# Mainboard_MCU_Func.net
KiCad netlist of a schematic drawn in Altium Designer
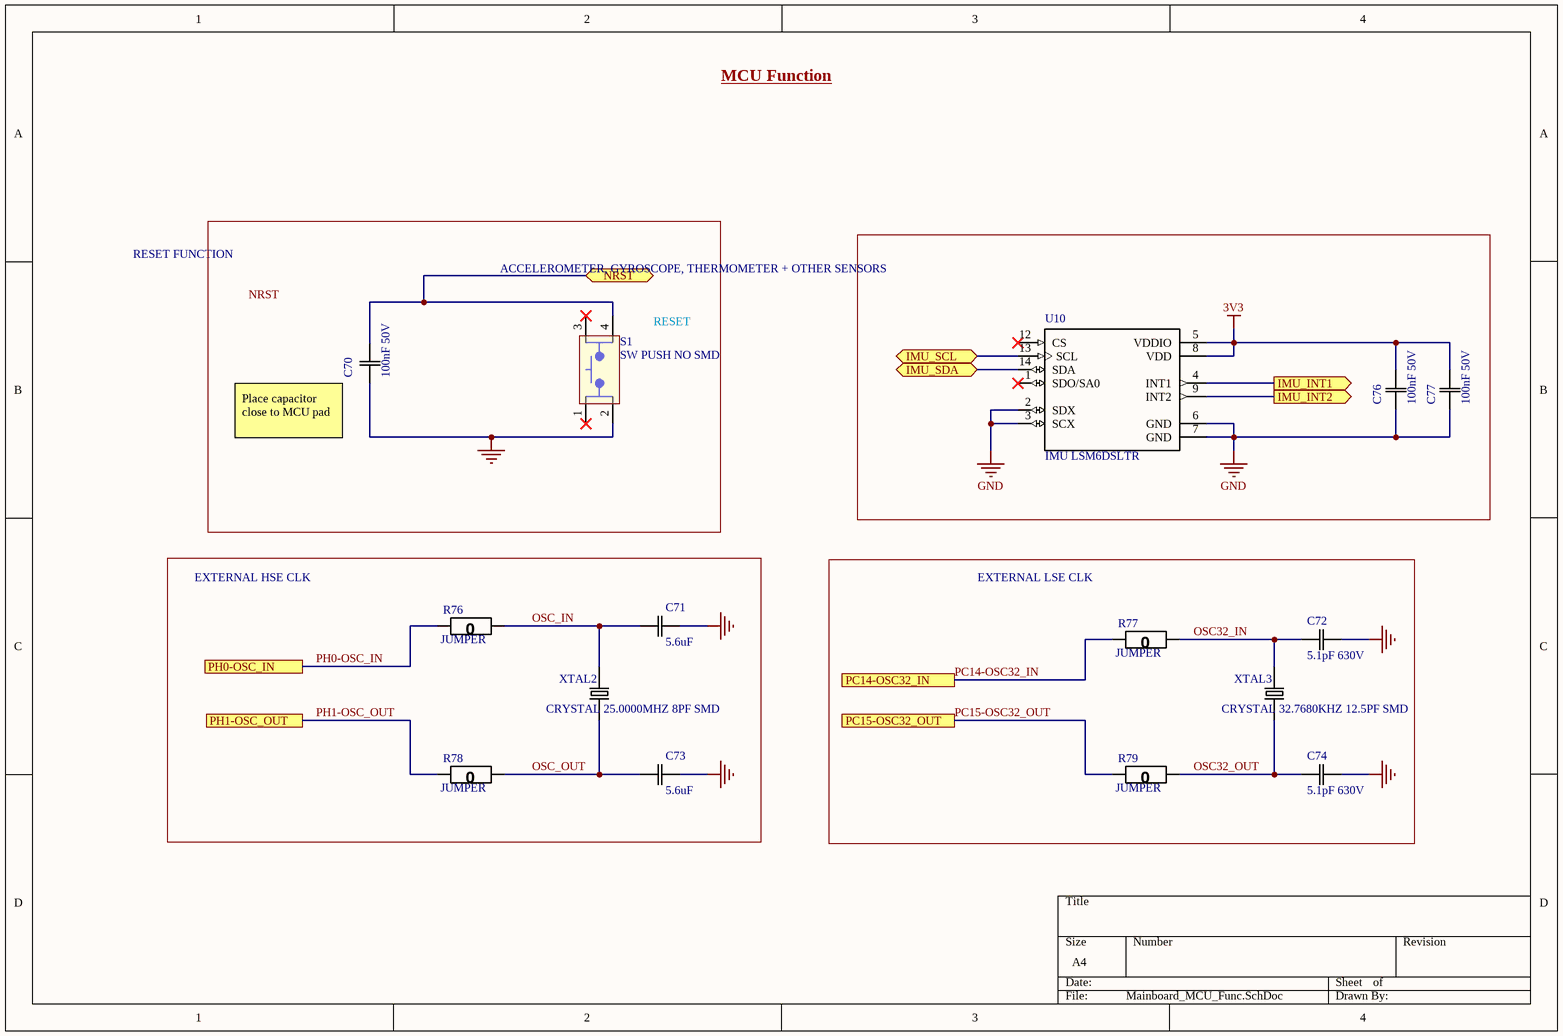
[diagram p0: Mainboard_MCU_Func.SchDoc]

(export (version "E")
  (design (tool "Eeschema 10.0.6"))
  (components
    (comp (ref "C70")
      (value "100nF 50V")
      (footprint "0805")
      (description "CAP CER 0.1UF 50V X7R 0805")
      (fields (field (name "TOLERANCE") "10%"))
      (libsource (lib "AltiumLibraries") (part "CAP 100nF 50V"))
    )
    (comp (ref "C71")
      (value "5.6uF")
      (footprint "0805")
      (description "CAP CER 5.6UF 6.3V X5R 0805")
      (fields (field (name "TOLERANCE") "10%"))
      (libsource (lib "AltiumLibraries") (part "CAP 5.6uF 6.3V"))
    )
    (comp (ref "C72")
      (value "5.1pF 630V")
      (footprint "0805")
      (description "CAP CER 5.1PF 630V C0G/NP0 0805")
      (fields (field (name "TOLERANCE") "10%"))
      (libsource (lib "AltiumLibraries") (part "CAP 5.1pF 630V"))
    )
    (comp (ref "C73")
      (value "5.6uF")
      (footprint "0805")
      (description "CAP CER 5.6UF 6.3V X5R 0805")
      (fields (field (name "TOLERANCE") "10%"))
      (libsource (lib "AltiumLibraries") (part "CAP 5.6uF 6.3V"))
    )
    (comp (ref "C74")
      (value "5.1pF 630V")
      (footprint "0805")
      (description "CAP CER 5.1PF 630V C0G/NP0 0805")
      (fields (field (name "TOLERANCE") "10%"))
      (libsource (lib "AltiumLibraries") (part "CAP 5.1pF 630V"))
    )
    (comp (ref "C76")
      (value "100nF 50V")
      (footprint "0805")
      (description "CAP CER 0.1UF 50V X7R 0805")
      (fields (field (name "TOLERANCE") "10%"))
      (libsource (lib "AltiumLibraries") (part "CAP 100nF 50V"))
    )
    (comp (ref "C77")
      (value "100nF 50V")
      (footprint "0805")
      (description "CAP CER 0.1UF 50V X7R 0805")
      (fields (field (name "TOLERANCE") "10%"))
      (libsource (lib "AltiumLibraries") (part "CAP 100nF 50V"))
    )
    (comp (ref "R76")
      (value "JUMPER")
      (footprint "0805")
      (description "RES SMD 0 OHM JUMPER GENERIC 0805")
      (libsource (lib "AltiumLibraries") (part "RES 0 JUMPER"))
    )
    (comp (ref "R77")
      (value "JUMPER")
      (footprint "0805")
      (description "RES SMD 0 OHM JUMPER GENERIC 0805")
      (libsource (lib "AltiumLibraries") (part "RES 0 JUMPER"))
    )
    (comp (ref "R78")
      (value "JUMPER")
      (footprint "0805")
      (description "RES SMD 0 OHM JUMPER GENERIC 0805")
      (libsource (lib "AltiumLibraries") (part "RES 0 JUMPER"))
    )
    (comp (ref "R79")
      (value "JUMPER")
      (footprint "0805")
      (description "RES SMD 0 OHM JUMPER GENERIC 0805")
      (libsource (lib "AltiumLibraries") (part "RES 0 JUMPER"))
    )
    (comp (ref "S1")
      (value "SW PUSH NO SMD")
      (footprint "TL3305")
      (description "Tactile Switch SPST-NO Top Actuated Surface Mount 12V 50mA")
      (fields (field (name "MF") "E-Switch") (field (name "MP") "TL3305BF260QG"))
      (libsource (lib "AltiumLibraries") (part "SW PUSH NO SMD"))
    )
    (comp (ref "U10")
      (value "IMU LSM6DSLTR")
      (footprint "LGA-14")
      (description "IMU ACCEL/GYRO I2C/SPI 14LGA")
      (fields (field (name "MP") "LSM6DSLTR") (field (name "MF") "STMicroelectronics"))
      (libsource (lib "AltiumLibraries") (part "IMU LSM6DSLTR"))
    )
    (comp (ref "XTAL2")
      (value "CRYSTAL 25.0000MHZ 8PF SMD")
      (footprint "SMD-2")
      (description "25MHz ±50ppm Crystal 8pF 70 Ohms 2-SMD, No Lead")
      (fields (field (name "MP") "NX5032GA-25.000000MHZ-LN-CD-1") (field (name "MF") "NDK America, Inc."))
      (libsource (lib "AltiumLibraries") (part "XTAL 25MHZ 8PF SMD"))
    )
    (comp (ref "XTAL3")
      (value "CRYSTAL 32.7680KHZ 12.5PF SMD")
      (footprint "SMD-2")
      (description "32.768kHz ±20ppm Crystal 12.5pF 70 kOhms 2-SMD, No Lead")
      (fields (field (name "MP") "NX3215SA-32.768K-STD-MUA-8") (field (name "MF") "NDK America, Inc."))
      (libsource (lib "AltiumLibraries") (part "XTAL 32.7680KHZ 12.5PF SMD"))
    )
  )
  (nets
    (net (code "1") (name "/IMU_INT1") (class "Default")
      (node (ref "U10") (pin "4") (pinfunction "INT1_4") (pintype "output"))
    )
    (net (code "2") (name "/IMU_INT2") (class "Default")
      (node (ref "U10") (pin "9") (pinfunction "INT2_9") (pintype "output"))
    )
    (net (code "3") (name "/IMU_SCL") (class "Default")
      (node (ref "U10") (pin "13") (pinfunction "SCL_13") (pintype "input"))
    )
    (net (code "4") (name "/IMU_SDA") (class "Default")
      (node (ref "U10") (pin "14") (pinfunction "SDA_14") (pintype "bidirectional"))
    )
    (net (code "5") (name "/NRST") (class "Default")
      (node (ref "C70") (pin "2") (pinfunction "C2_2") (pintype "passive"))
      (node (ref "S1") (pin "4") (pinfunction "4_4") (pintype "passive"))
    )
    (net (code "6") (name "/OSC32_IN") (class "Default")
      (node (ref "C72") (pin "1") (pinfunction "C1_1") (pintype "passive"))
      (node (ref "R77") (pin "1") (pinfunction "R1_1") (pintype "passive"))
      (node (ref "XTAL3") (pin "2") (pinfunction "2_2") (pintype "passive"))
    )
    (net (code "7") (name "/OSC32_OUT") (class "Default")
      (node (ref "C74") (pin "1") (pinfunction "C1_1") (pintype "passive"))
      (node (ref "R79") (pin "1") (pinfunction "R1_1") (pintype "passive"))
      (node (ref "XTAL3") (pin "1") (pinfunction "1_1") (pintype "passive"))
    )
    (net (code "8") (name "/OSC_IN") (class "Default")
      (node (ref "C71") (pin "1") (pinfunction "C1_1") (pintype "passive"))
      (node (ref "R76") (pin "1") (pinfunction "R1_1") (pintype "passive"))
      (node (ref "XTAL2") (pin "2") (pinfunction "2_2") (pintype "passive"))
    )
    (net (code "9") (name "/OSC_OUT") (class "Default")
      (node (ref "C73") (pin "1") (pinfunction "C1_1") (pintype "passive"))
      (node (ref "R78") (pin "1") (pinfunction "R1_1") (pintype "passive"))
      (node (ref "XTAL2") (pin "1") (pinfunction "1_1") (pintype "passive"))
    )
    (net (code "10") (name "/PC14-OSC32_IN") (class "Default")
      (node (ref "R77") (pin "2") (pinfunction "R2_2") (pintype "passive"))
    )
    (net (code "11") (name "/PC15-OSC32_OUT") (class "Default")
      (node (ref "R79") (pin "2") (pinfunction "R2_2") (pintype "passive"))
    )
    (net (code "12") (name "/PH0-OSC_IN") (class "Default")
      (node (ref "R76") (pin "2") (pinfunction "R2_2") (pintype "passive"))
    )
    (net (code "13") (name "/PH1-OSC_OUT") (class "Default")
      (node (ref "R78") (pin "2") (pinfunction "R2_2") (pintype "passive"))
    )
    (net (code "14") (name "3V3") (class "Default")
      (node (ref "C76") (pin "2") (pinfunction "C2_2") (pintype "passive"))
      (node (ref "C77") (pin "2") (pinfunction "C2_2") (pintype "passive"))
      (node (ref "U10") (pin "5") (pinfunction "VDDIO_5") (pintype "power_in"))
      (node (ref "U10") (pin "8") (pinfunction "VDD_8") (pintype "power_in"))
    )
    (net (code "15") (name "GND") (class "Default")
      (node (ref "C70") (pin "1") (pinfunction "C1_1") (pintype "passive"))
      (node (ref "C71") (pin "2") (pinfunction "C2_2") (pintype "passive"))
      (node (ref "C72") (pin "2") (pinfunction "C2_2") (pintype "passive"))
      (node (ref "C73") (pin "2") (pinfunction "C2_2") (pintype "passive"))
      (node (ref "C74") (pin "2") (pinfunction "C2_2") (pintype "passive"))
      (node (ref "C76") (pin "1") (pinfunction "C1_1") (pintype "passive"))
      (node (ref "C77") (pin "1") (pinfunction "C1_1") (pintype "passive"))
      (node (ref "S1") (pin "2") (pinfunction "2_2") (pintype "passive"))
      (node (ref "U10") (pin "2") (pinfunction "SDX_2") (pintype "bidirectional"))
      (node (ref "U10") (pin "3") (pinfunction "SCX_3") (pintype "bidirectional"))
      (node (ref "U10") (pin "6") (pinfunction "GND_6") (pintype "power_in"))
      (node (ref "U10") (pin "7") (pinfunction "GND_7") (pintype "power_in"))
    )
    (net (code "16") (name "unconnected-(S1-Pad1)") (class "Default")
      (node (ref "S1") (pin "1") (pinfunction "1_1") (pintype "passive+no_connect"))
    )
    (net (code "17") (name "unconnected-(S1-Pad3)") (class "Default")
      (node (ref "S1") (pin "3") (pinfunction "3_3") (pintype "passive+no_connect"))
    )
    (net (code "18") (name "unconnected-(U10-CS-Pad12)") (class "Default")
      (node (ref "U10") (pin "12") (pinfunction "CS_12") (pintype "input+no_connect"))
    )
    (net (code "19") (name "unconnected-(U10-SDO{slash}SA0-Pad1)") (class "Default")
      (node (ref "U10") (pin "1") (pinfunction "SDO/SA0_1") (pintype "bidirectional+no_connect"))
    )
  )
)
